# deepshark_sensor.net
KiCad netlist of a schematic drawn in Altium Designer
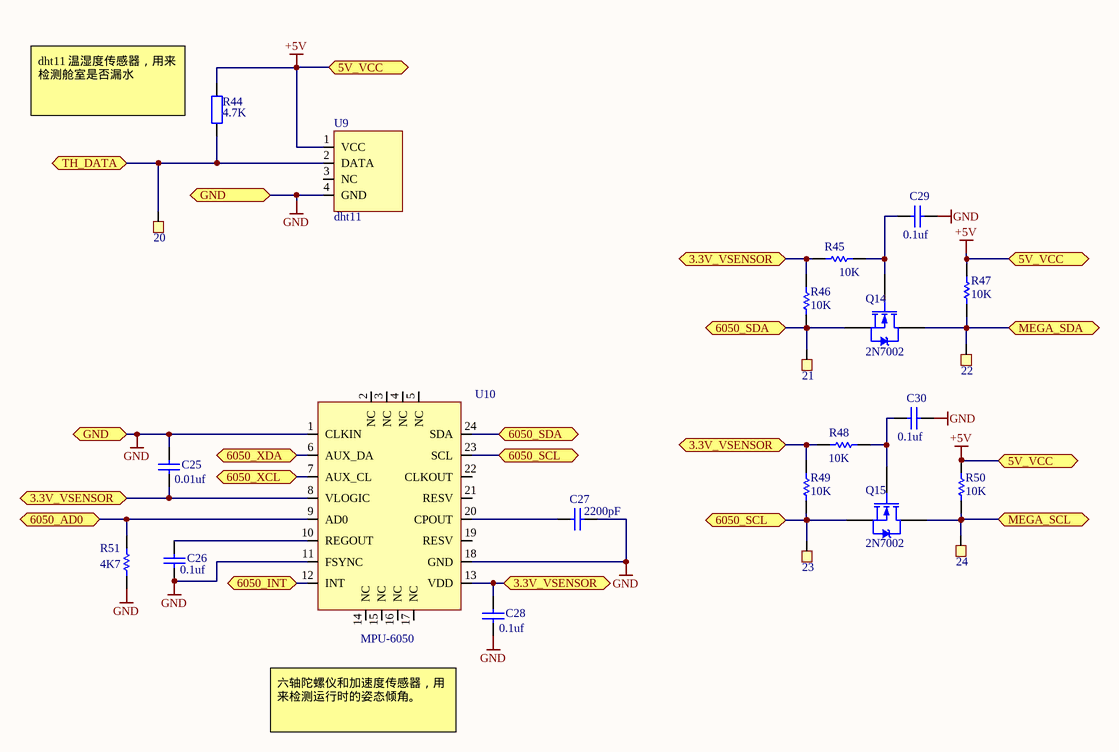
[diagram p0: deepshark_sensor.SchDoc]

(export (version "E")
  (design (tool "Eeschema 10.0.6"))
  (components
    (comp (ref "20") (value "TP") (footprint "TestPoint") (libsource (lib "deepshark_sch_lib") (part "TP")))
    (comp (ref "21") (value "TP") (footprint "TestPoint") (libsource (lib "deepshark_sch_lib") (part "TP")))
    (comp (ref "22") (value "TP") (footprint "TestPoint") (libsource (lib "deepshark_sch_lib") (part "TP")))
    (comp (ref "23") (value "TP") (footprint "TestPoint") (libsource (lib "deepshark_sch_lib") (part "TP")))
    (comp (ref "24") (value "TP") (footprint "TestPoint") (libsource (lib "deepshark_sch_lib") (part "TP")))
    (comp (ref "C25")
      (value "0.01uf")
      (footprint "6-0805_M")
      (description "Capacitor")
      (fields (field (name "Comment") "Cap") (field (name "PUBLISHER") "Altium Limited"))
      (libsource (lib "Miscellaneous Devices") (part "Cap"))
    )
    (comp (ref "C26")
      (value "0.1uf")
      (footprint "6-0805_M")
      (description "Capacitor")
      (fields (field (name "Comment") "Cap") (field (name "PUBLISHER") "Altium Limited"))
      (libsource (lib "Miscellaneous Devices") (part "Cap"))
    )
    (comp (ref "C27")
      (value "2200pF")
      (footprint "my0603")
      (description "Capacitor")
      (fields (field (name "Comment") "Cap") (field (name "PUBLISHER") "Altium Limited"))
      (libsource (lib "Miscellaneous Devices") (part "Cap"))
    )
    (comp (ref "C28")
      (value "0.1uf")
      (footprint "6-0805_M")
      (description "Capacitor")
      (fields (field (name "Comment") "Cap") (field (name "PUBLISHER") "Altium Limited"))
      (libsource (lib "Miscellaneous Devices") (part "Cap"))
    )
    (comp (ref "C29")
      (value "0.1uf")
      (footprint "6-0805_M")
      (description "Capacitor")
      (fields (field (name "Comment") "Cap") (field (name "PUBLISHER") "Altium Limited"))
      (libsource (lib "Miscellaneous Devices") (part "Cap"))
    )
    (comp (ref "C30")
      (value "0.1uf")
      (footprint "6-0805_M")
      (description "Capacitor")
      (fields (field (name "Comment") "Cap") (field (name "PUBLISHER") "Altium Limited"))
      (libsource (lib "Miscellaneous Devices") (part "Cap"))
    )
    (comp (ref "Q14")
      (value "2N7002")
      (footprint "2N7002")
      (description "N-Channel Power MOSFET")
      (fields (field (name "PUBLISHER") "Altium Limited"))
      (libsource (lib "Miscellaneous Devices") (part "NMOS-2"))
    )
    (comp (ref "Q15")
      (value "2N7002")
      (footprint "2N7002")
      (description "N-Channel Power MOSFET")
      (fields (field (name "PUBLISHER") "Altium Limited"))
      (libsource (lib "Miscellaneous Devices") (part "NMOS-2"))
    )
    (comp (ref "R44")
      (value "4.7K")
      (footprint "6-0805_M")
      (description "Resistor")
      (fields (field (name "Comment") "Res2") (field (name "PUBLISHER") "Altium Limited"))
      (libsource (lib "Miscellaneous Devices") (part "Res2"))
    )
    (comp (ref "R45")
      (value "10K")
      (footprint "6-0805_M")
      (description "Resistor")
      (fields (field (name "Comment") "Res1") (field (name "PUBLISHER") "Altium Limited"))
      (libsource (lib "Miscellaneous Devices") (part "Res1"))
    )
    (comp (ref "R46")
      (value "10K")
      (footprint "6-0805_M")
      (description "Resistor")
      (fields (field (name "Comment") "Res1") (field (name "PUBLISHER") "Altium Limited"))
      (libsource (lib "Miscellaneous Devices") (part "Res1"))
    )
    (comp (ref "R47")
      (value "10K")
      (footprint "6-0805_M")
      (description "Resistor")
      (fields (field (name "Comment") "Res1") (field (name "PUBLISHER") "Altium Limited"))
      (libsource (lib "Miscellaneous Devices") (part "Res1"))
    )
    (comp (ref "R48")
      (value "10K")
      (footprint "6-0805_M")
      (description "Resistor")
      (fields (field (name "Comment") "Res1") (field (name "PUBLISHER") "Altium Limited"))
      (libsource (lib "Miscellaneous Devices") (part "Res1"))
    )
    (comp (ref "R49")
      (value "10K")
      (footprint "6-0805_M")
      (description "Resistor")
      (fields (field (name "Comment") "Res1") (field (name "PUBLISHER") "Altium Limited"))
      (libsource (lib "Miscellaneous Devices") (part "Res1"))
    )
    (comp (ref "R50")
      (value "10K")
      (footprint "6-0805_M")
      (description "Resistor")
      (fields (field (name "Comment") "Res1") (field (name "PUBLISHER") "Altium Limited"))
      (libsource (lib "Miscellaneous Devices") (part "Res1"))
    )
    (comp (ref "R51")
      (value "4K7")
      (footprint "6-0805_M")
      (description "Resistor")
      (fields (field (name "Comment") "Res1") (field (name "PUBLISHER") "Altium Limited"))
      (libsource (lib "Miscellaneous Devices") (part "Res1"))
    )
    (comp (ref "U9")
      (value "dht11")
      (footprint "DHT11")
      (libsource (lib "deepshark_sch_lib") (part "dht411"))
    )
    (comp (ref "U10")
      (value "MPU-6050")
      (footprint "mpu6050")
      (libsource (lib "deepshark_sch_lib") (part "MPU-6050"))
    )
  )
  (nets
    (net (code "1") (name "+5V") (class "Default")
      (node (ref "R44") (pin "2") (pinfunction "2_2") (pintype "passive"))
      (node (ref "R47") (pin "2") (pinfunction "2_2") (pintype "passive"))
      (node (ref "R50") (pin "2") (pinfunction "2_2") (pintype "passive"))
      (node (ref "U9") (pin "1") (pinfunction "VCC_1") (pintype "passive"))
    )
    (net (code "2") (name "/3.3V_VSENSOR") (class "Default")
      (node (ref "C25") (pin "2") (pinfunction "2_2") (pintype "passive"))
      (node (ref "C28") (pin "1") (pinfunction "1_1") (pintype "passive"))
      (node (ref "R45") (pin "1") (pinfunction "1_1") (pintype "passive"))
      (node (ref "R46") (pin "2") (pinfunction "2_2") (pintype "passive"))
      (node (ref "R48") (pin "1") (pinfunction "1_1") (pintype "passive"))
      (node (ref "R49") (pin "2") (pinfunction "2_2") (pintype "passive"))
      (node (ref "U10") (pin "13") (pinfunction "VDD_13") (pintype "passive"))
      (node (ref "U10") (pin "8") (pinfunction "VLOGIC_8") (pintype "passive"))
    )
    (net (code "3") (name "/6050_AD0") (class "Default")
      (node (ref "R51") (pin "2") (pinfunction "2_2") (pintype "passive"))
      (node (ref "U10") (pin "9") (pinfunction "AD0_9") (pintype "passive"))
    )
    (net (code "4") (name "/6050_INT") (class "Default")
      (node (ref "U10") (pin "12") (pinfunction "INT_12") (pintype "passive"))
    )
    (net (code "5") (name "/6050_SCL") (class "Default")
      (node (ref "23") (pin "1") (pinfunction "1_1") (pintype "passive"))
      (node (ref "Q15") (pin "3") (pinfunction "S_3") (pintype "passive"))
      (node (ref "R49") (pin "1") (pinfunction "1_1") (pintype "passive"))
      (node (ref "U10") (pin "23") (pinfunction "SCL_23") (pintype "passive"))
    )
    (net (code "6") (name "/6050_SDA") (class "Default")
      (node (ref "21") (pin "1") (pinfunction "1_1") (pintype "passive"))
      (node (ref "Q14") (pin "3") (pinfunction "S_3") (pintype "passive"))
      (node (ref "R46") (pin "1") (pinfunction "1_1") (pintype "passive"))
      (node (ref "U10") (pin "24") (pinfunction "SDA_24") (pintype "passive"))
    )
    (net (code "7") (name "/6050_XCL") (class "Default")
      (node (ref "U10") (pin "7") (pinfunction "AUX_CL_7") (pintype "passive"))
    )
    (net (code "8") (name "/6050_XDA") (class "Default")
      (node (ref "U10") (pin "6") (pinfunction "AUX_DA_6") (pintype "passive"))
    )
    (net (code "9") (name "/MEGA_SCL") (class "Default")
      (node (ref "24") (pin "1") (pinfunction "1_1") (pintype "passive"))
      (node (ref "Q15") (pin "2") (pinfunction "D_2") (pintype "passive"))
      (node (ref "R50") (pin "1") (pinfunction "1_1") (pintype "passive"))
    )
    (net (code "10") (name "/MEGA_SDA") (class "Default")
      (node (ref "22") (pin "1") (pinfunction "1_1") (pintype "passive"))
      (node (ref "Q14") (pin "2") (pinfunction "D_2") (pintype "passive"))
      (node (ref "R47") (pin "1") (pinfunction "1_1") (pintype "passive"))
    )
    (net (code "11") (name "/TH_DATA") (class "Default")
      (node (ref "20") (pin "1") (pinfunction "1_1") (pintype "passive"))
      (node (ref "R44") (pin "1") (pinfunction "1_1") (pintype "passive"))
      (node (ref "U9") (pin "2") (pinfunction "DATA_2") (pintype "passive"))
    )
    (net (code "12") (name "GND") (class "Default")
      (node (ref "C25") (pin "1") (pinfunction "1_1") (pintype "passive"))
      (node (ref "C26") (pin "1") (pinfunction "1_1") (pintype "passive"))
      (node (ref "C27") (pin "2") (pinfunction "2_2") (pintype "passive"))
      (node (ref "C28") (pin "2") (pinfunction "2_2") (pintype "passive"))
      (node (ref "C29") (pin "2") (pinfunction "2_2") (pintype "passive"))
      (node (ref "C30") (pin "2") (pinfunction "2_2") (pintype "passive"))
      (node (ref "R51") (pin "1") (pinfunction "1_1") (pintype "passive"))
      (node (ref "U10") (pin "1") (pinfunction "CLKIN_1") (pintype "passive"))
      (node (ref "U10") (pin "11") (pinfunction "FSYNC_11") (pintype "passive"))
      (node (ref "U10") (pin "18") (pinfunction "GND_18") (pintype "passive"))
      (node (ref "U9") (pin "4") (pinfunction "GND_4") (pintype "passive"))
    )
    (net (code "13") (name "Net-(Q14-G)") (class "Default")
      (node (ref "C29") (pin "1") (pinfunction "1_1") (pintype "passive"))
      (node (ref "Q14") (pin "1") (pinfunction "G_1") (pintype "passive"))
      (node (ref "R45") (pin "2") (pinfunction "2_2") (pintype "passive"))
    )
    (net (code "14") (name "Net-(Q15-G)") (class "Default")
      (node (ref "C30") (pin "1") (pinfunction "1_1") (pintype "passive"))
      (node (ref "Q15") (pin "1") (pinfunction "G_1") (pintype "passive"))
      (node (ref "R48") (pin "2") (pinfunction "2_2") (pintype "passive"))
    )
    (net (code "15") (name "Net-(U10-CPOUT)") (class "Default")
      (node (ref "C27") (pin "1") (pinfunction "1_1") (pintype "passive"))
      (node (ref "U10") (pin "20") (pinfunction "CPOUT_20") (pintype "passive"))
    )
    (net (code "16") (name "Net-(U10-REGOUT)") (class "Default")
      (node (ref "C26") (pin "2") (pinfunction "2_2") (pintype "passive"))
      (node (ref "U10") (pin "10") (pinfunction "REGOUT_10") (pintype "passive"))
    )
    (net (code "17") (name "unconnected-(U9-NC-Pad3)") (class "Default")
      (node (ref "U9") (pin "3") (pinfunction "NC_3") (pintype "passive"))
    )
    (net (code "18") (name "unconnected-(U10-CLKOUT-Pad22)") (class "Default")
      (node (ref "U10") (pin "22") (pinfunction "CLKOUT_22") (pintype "passive"))
    )
    (net (code "19") (name "unconnected-(U10-NC-Pad2)") (class "Default")
      (node (ref "U10") (pin "2") (pinfunction "NC_2") (pintype "passive"))
    )
    (net (code "20") (name "unconnected-(U10-NC-Pad3)") (class "Default")
      (node (ref "U10") (pin "3") (pinfunction "NC_3") (pintype "passive"))
    )
    (net (code "21") (name "unconnected-(U10-NC-Pad4)") (class "Default")
      (node (ref "U10") (pin "4") (pinfunction "NC_4") (pintype "passive"))
    )
    (net (code "22") (name "unconnected-(U10-NC-Pad5)") (class "Default")
      (node (ref "U10") (pin "5") (pinfunction "NC_5") (pintype "passive"))
    )
    (net (code "23") (name "unconnected-(U10-NC-Pad14)") (class "Default")
      (node (ref "U10") (pin "14") (pinfunction "NC_14") (pintype "passive"))
    )
    (net (code "24") (name "unconnected-(U10-NC-Pad15)") (class "Default")
      (node (ref "U10") (pin "15") (pinfunction "NC_15") (pintype "passive"))
    )
    (net (code "25") (name "unconnected-(U10-NC-Pad16)") (class "Default")
      (node (ref "U10") (pin "16") (pinfunction "NC_16") (pintype "passive"))
    )
    (net (code "26") (name "unconnected-(U10-NC-Pad17)") (class "Default")
      (node (ref "U10") (pin "17") (pinfunction "NC_17") (pintype "passive"))
    )
    (net (code "27") (name "unconnected-(U10-RESV-Pad19)") (class "Default")
      (node (ref "U10") (pin "19") (pinfunction "RESV_19") (pintype "passive"))
    )
    (net (code "28") (name "unconnected-(U10-RESV-Pad21)") (class "Default")
      (node (ref "U10") (pin "21") (pinfunction "RESV_21") (pintype "passive"))
    )
  )
)
